# SCH_Alarm-PCB_2024-07-23.net
KiCad netlist of a schematic drawn in EasyEDA
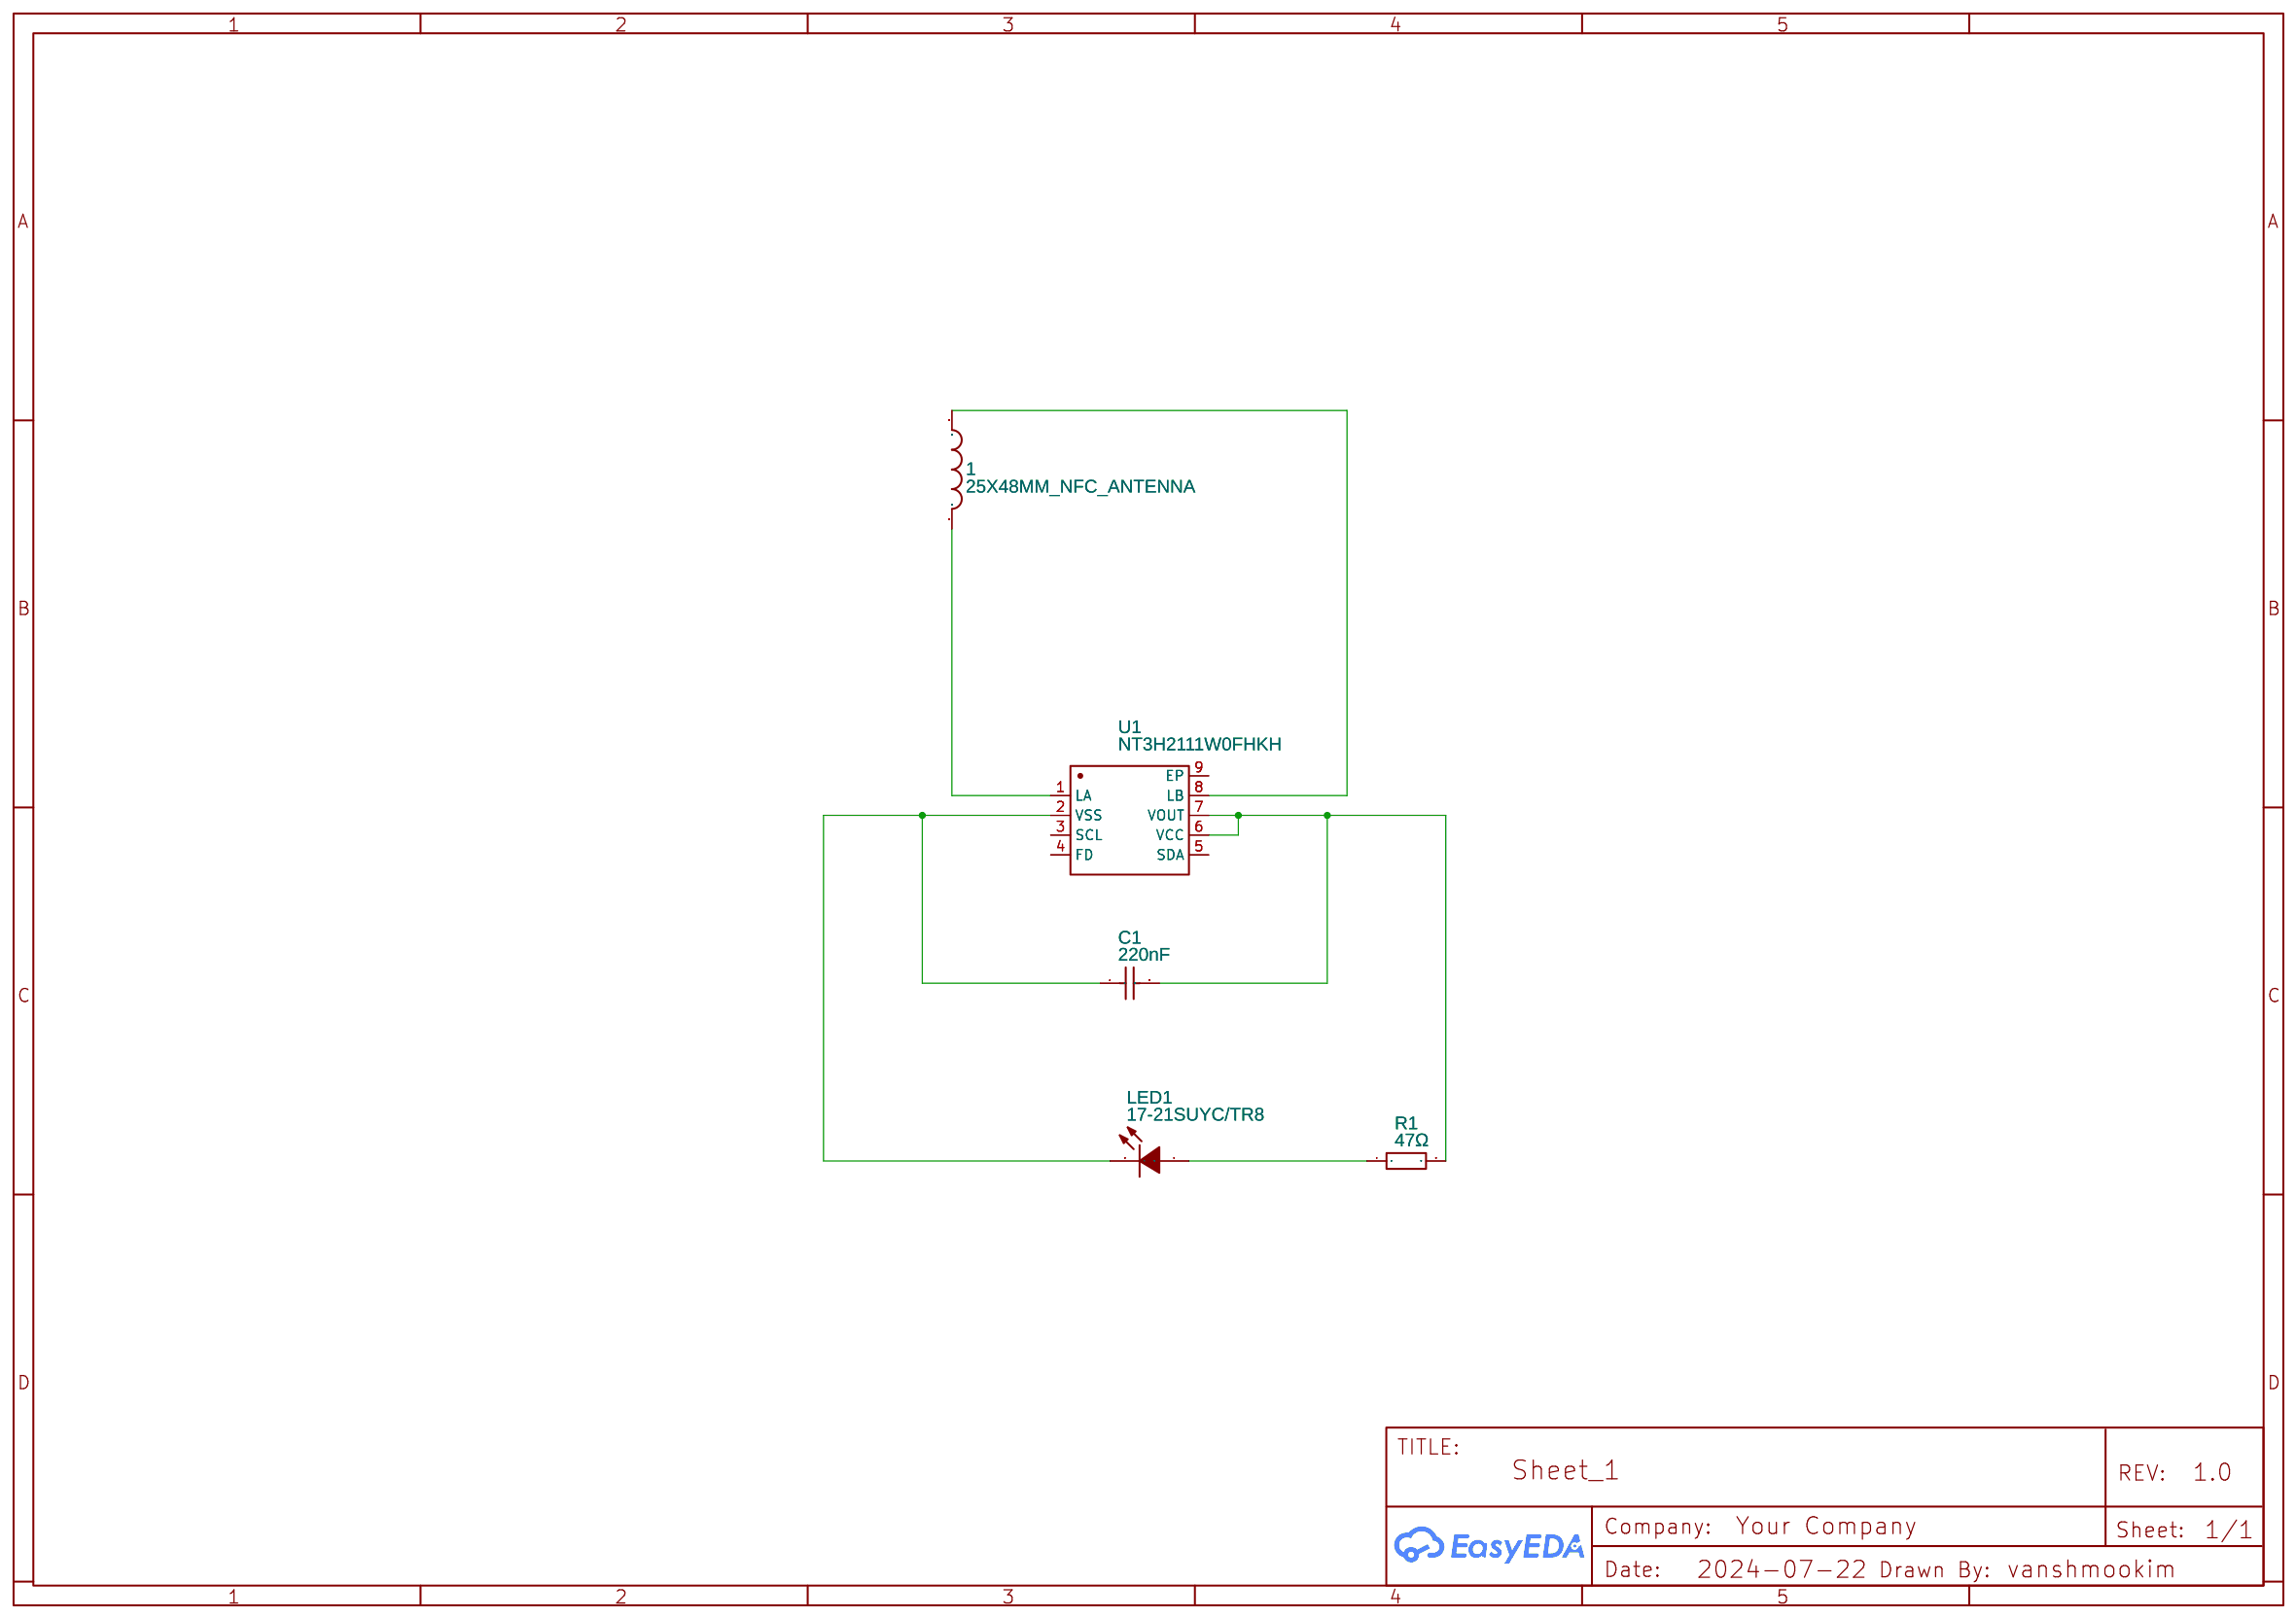
[diagram p0: schematic sheet]

(export (version "E")
  (design (tool "Eeschema 10.0.6"))
  (components
    (comp (ref "1") (value "25X48MM_NFC_ANTENNA") (libsource (lib "") (part "25X48MM_NFC_ANTENNA")))
    (comp (ref "C1")
      (value "220nF")
      (fields
        (field (name "Manufacturer Part") "CL10B224KA8NNNC")
        (field (name "Manufacturer") "SAMSUNG(三星)")
      )
      (libsource (lib "") (part "CL10B224KA8NNNC"))
    )
    (comp (ref "LED1")
      (value "17-21SUYC/TR8")
      (fields (field (name "Manufacturer Part") "KT-0805黄灯") (field (name "Manufacturer") "KENTO"))
      (libsource (lib "") (part "17-21SUYC/TR8"))
    )
    (comp (ref "R1")
      (value "47Ω")
      (fields
        (field (name "Manufacturer Part") "0603WAF470JT5E")
        (field (name "Manufacturer") "UNI-ROYAL(厚声)")
      )
      (libsource (lib "") (part "0603WAF470JT5E"))
    )
    (comp (ref "U1")
      (value "NT3H2111W0FHKH")
      (fields (field (name "Manufacturer") "NXP(恩智浦)"))
      (libsource (lib "") (part "NT3H2111W0FHKH"))
    )
  )
  (nets
    (net (code "1") (name "Net-(LED1-+)") (class "Default")
      (node (ref "LED1") (pin "1") (pinfunction "+_1") (pintype "unspecified"))
      (node (ref "R1") (pin "1") (pinfunction "1_1") (pintype "input"))
    )
    (net (code "2") (name "Net-(LED1--)") (class "Default")
      (node (ref "C1") (pin "1") (pinfunction "1_1") (pintype "input"))
      (node (ref "LED1") (pin "2") (pinfunction "-_2") (pintype "unspecified"))
      (node (ref "U1") (pin "2") (pinfunction "VSS_2") (pintype "unspecified"))
    )
    (net (code "3") (name "Net-(U1-LA)") (class "Default")
      (node (ref "1") (pin "P$2") (pinfunction "P$2_P$2") (pintype "bidirectional"))
      (node (ref "U1") (pin "1") (pinfunction "LA_1") (pintype "unspecified"))
    )
    (net (code "4") (name "Net-(U1-LB)") (class "Default")
      (node (ref "1") (pin "P$1") (pinfunction "P$1_P$1") (pintype "bidirectional"))
      (node (ref "U1") (pin "8") (pinfunction "LB_8") (pintype "unspecified"))
    )
    (net (code "5") (name "Net-(U1-VCC)") (class "Default")
      (node (ref "C1") (pin "2") (pinfunction "2_2") (pintype "input"))
      (node (ref "R1") (pin "2") (pinfunction "2_2") (pintype "input"))
      (node (ref "U1") (pin "6") (pinfunction "VCC_6") (pintype "unspecified"))
      (node (ref "U1") (pin "7") (pinfunction "VOUT_7") (pintype "unspecified"))
    )
    (net (code "6") (name "unconnected-(U1-EP-Pad9)") (class "Default")
      (node (ref "U1") (pin "9") (pinfunction "EP_9") (pintype "unspecified"))
    )
    (net (code "7") (name "unconnected-(U1-FD-Pad4)") (class "Default")
      (node (ref "U1") (pin "4") (pinfunction "FD_4") (pintype "unspecified"))
    )
    (net (code "8") (name "unconnected-(U1-SCL-Pad3)") (class "Default")
      (node (ref "U1") (pin "3") (pinfunction "SCL_3") (pintype "unspecified"))
    )
    (net (code "9") (name "unconnected-(U1-SDA-Pad5)") (class "Default")
      (node (ref "U1") (pin "5") (pinfunction "SDA_5") (pintype "unspecified"))
    )
  )
)
